# DS18B20_with_DS2480B_MAX233_V4.net
KiCad netlist of a schematic drawn in EAGLE
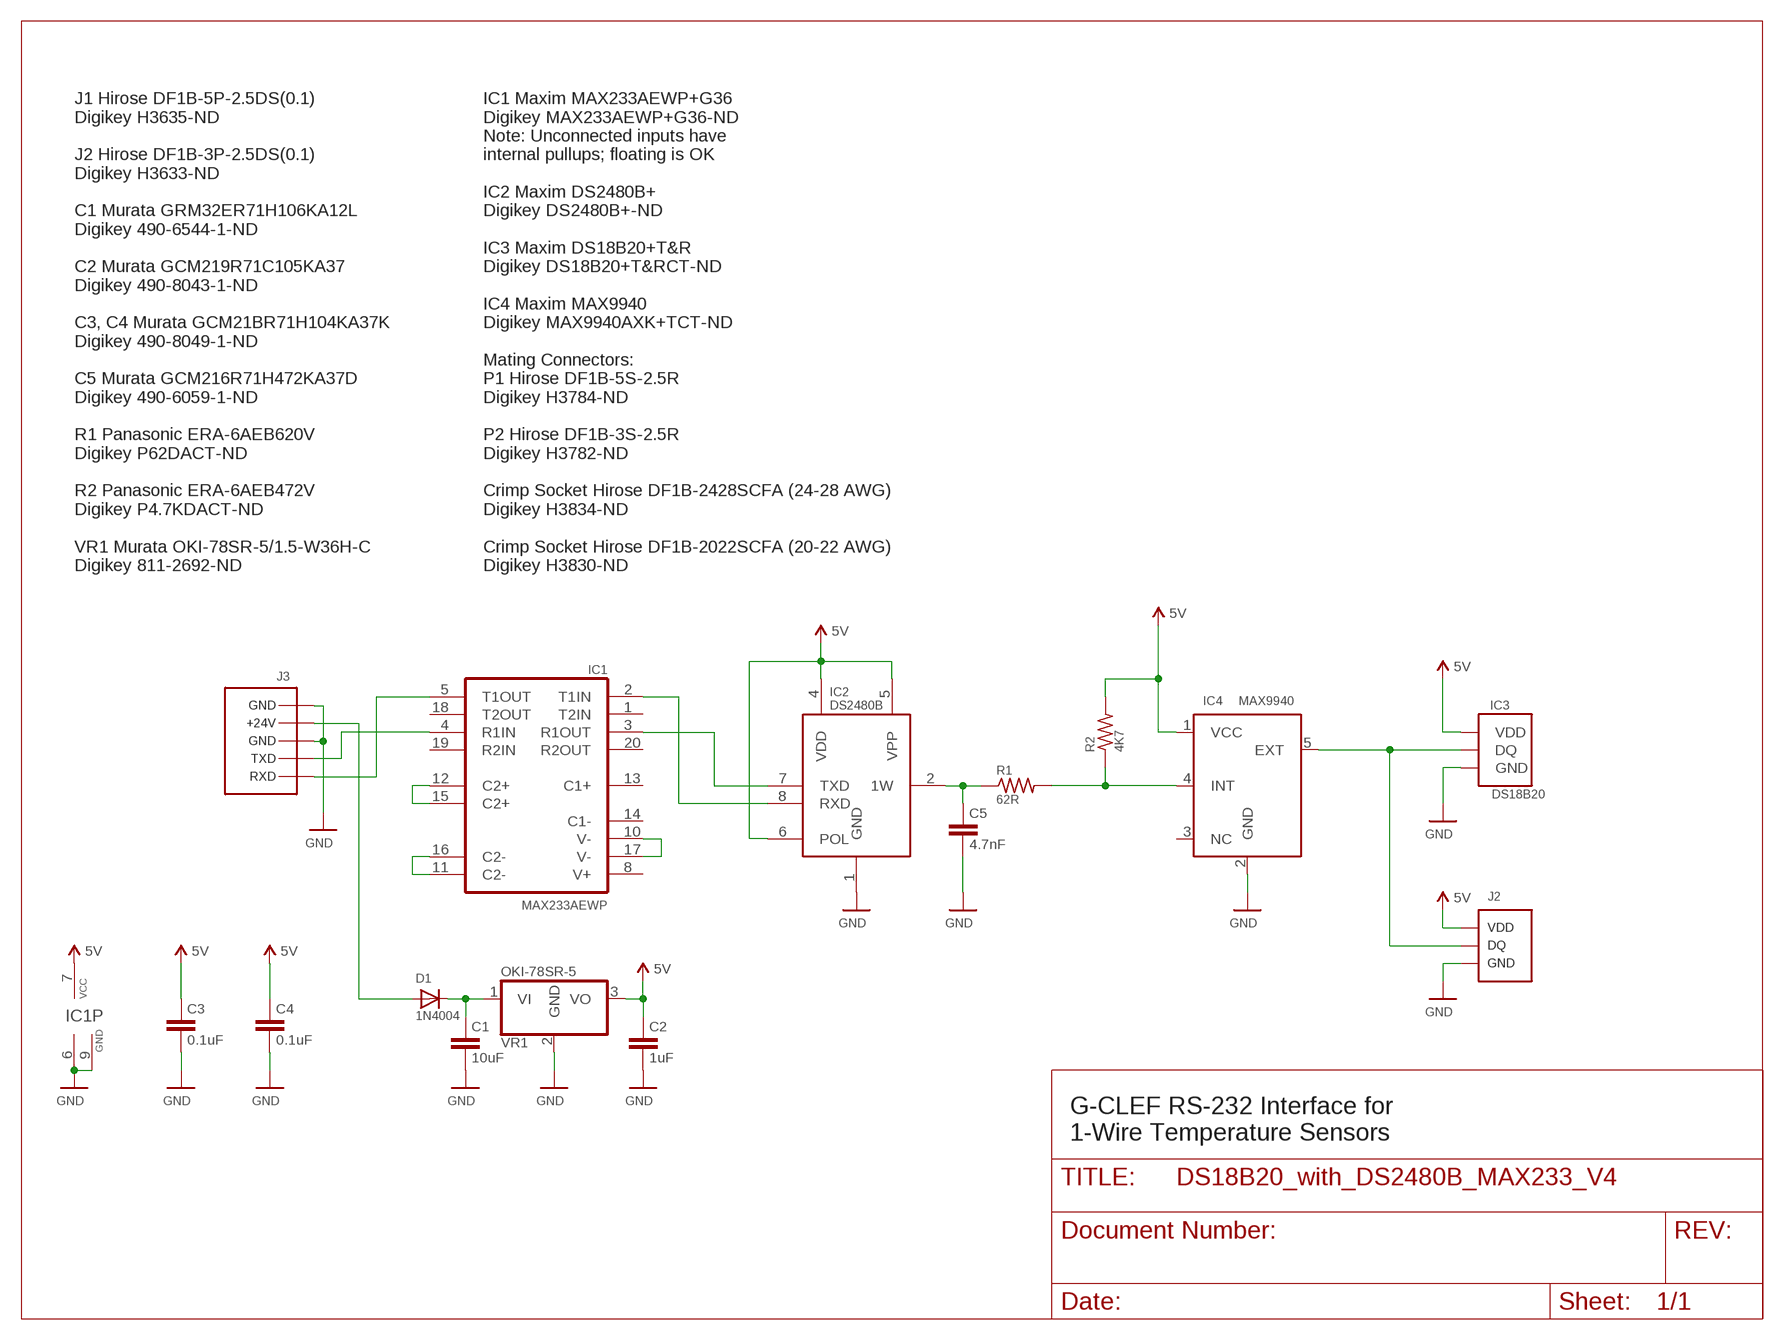
[diagram p0: schematic, sheet 1]

(export (version "E")
  (design (tool "Eeschema 10.0.6"))
  (components
    (comp (ref "C1")
      (value "10uF")
      (footprint "eagle-import:CAPC3225X270N")
      (libsource (lib "eagle-import") (part "C-UNPOL1210-CAP"))
    )
    (comp (ref "C2")
      (value "1uF")
      (footprint "eagle-import:CAPC2013X135N")
      (libsource (lib "eagle-import") (part "C-UNPOL0805-CAP"))
    )
    (comp (ref "C3")
      (value "0.1uF")
      (footprint "eagle-import:CAPC2013X135N")
      (libsource (lib "eagle-import") (part "C-UNPOL0805-CAP"))
    )
    (comp (ref "C4")
      (value "0.1uF")
      (footprint "eagle-import:CAPC2013X135N")
      (libsource (lib "eagle-import") (part "C-UNPOL0805-CAP"))
    )
    (comp (ref "C5")
      (value "4.7nF")
      (footprint "eagle-import:CAPC2013X135N")
      (libsource (lib "eagle-import") (part "C-UNPOL0805-CAP"))
    )
    (comp (ref "D1")
      (value "1N4004")
      (footprint "eagle-import:DO41-10")
      (libsource (lib "eagle-import") (part "1N4004"))
    )
    (comp (ref "IC1")
      (value "MAX233AEWP")
      (footprint "eagle-import:SO20L")
      (fields (field (name "MPN") "MAX233AEWP+G36"))
      (libsource (lib "eagle-import") (part "MAX233AEWP"))
    )
    (comp (ref "IC2")
      (value "DS2480B")
      (footprint "eagle-import:SO08")
      (libsource (lib "eagle-import") (part "DS2480B"))
    )
    (comp (ref "IC3")
      (value "DS18B20")
      (footprint "eagle-import:TO92-")
      (libsource (lib "eagle-import") (part "DS18B20"))
    )
    (comp (ref "IC4")
      (value "MAX9940")
      (footprint "eagle-import:SC70-5L")
      (libsource (lib "eagle-import") (part "MAX9940"))
    )
    (comp (ref "J2")
      (value "DF1B-3P")
      (footprint "eagle-import:DF1B-3P")
      (libsource (lib "eagle-import") (part "DF1B-3P"))
    )
    (comp (ref "J3")
      (value "DF1B-5P")
      (footprint "eagle-import:DF1B-5P")
      (libsource (lib "eagle-import") (part "DF1B-5P"))
    )
    (comp (ref "R1")
      (value "62R")
      (footprint "eagle-import:RESISTOR-0805")
      (libsource (lib "eagle-import") (part "RESISTOR-0805"))
    )
    (comp (ref "R2")
      (value "4K7")
      (footprint "eagle-import:RESISTOR-0805")
      (libsource (lib "eagle-import") (part "RESISTOR-0805"))
    )
    (comp (ref "VR1")
      (value "OKI-78SR-5")
      (footprint "eagle-import:OKI-78SR")
      (libsource (lib "eagle-import") (part "OKI-78SRH"))
    )
  )
  (nets
    (net (code "1") (name "5V") (class "Default")
      (node (ref "C2") (pin "1") (pinfunction "1_1") (pintype "passive"))
      (node (ref "C3") (pin "1") (pinfunction "1_1") (pintype "passive"))
      (node (ref "C4") (pin "1") (pinfunction "1_1") (pintype "passive"))
      (node (ref "IC1") (pin "7") (pinfunction "VCC_7") (pintype "power_in"))
      (node (ref "IC2") (pin "4") (pinfunction "VDD_4") (pintype "power_in"))
      (node (ref "IC2") (pin "5") (pinfunction "VPP_5") (pintype "power_in"))
      (node (ref "IC2") (pin "6") (pinfunction "POL_6") (pintype "input"))
      (node (ref "IC3") (pin "3") (pinfunction "VDD_3") (pintype "bidirectional"))
      (node (ref "IC4") (pin "1") (pinfunction "VCC_1") (pintype "power_in"))
      (node (ref "J2") (pin "P$3") (pinfunction "P$3_P$3") (pintype "bidirectional"))
      (node (ref "R2") (pin "2") (pinfunction "2_2") (pintype "passive"))
      (node (ref "VR1") (pin "3") (pinfunction "VO_3") (pintype "passive"))
    )
    (net (code "2") (name "GND") (class "Default")
      (node (ref "C1") (pin "2") (pinfunction "2_2") (pintype "passive"))
      (node (ref "C2") (pin "2") (pinfunction "2_2") (pintype "passive"))
      (node (ref "C3") (pin "2") (pinfunction "2_2") (pintype "passive"))
      (node (ref "C4") (pin "2") (pinfunction "2_2") (pintype "passive"))
      (node (ref "C5") (pin "2") (pinfunction "2_2") (pintype "passive"))
      (node (ref "IC1") (pin "6") (pinfunction "GND_6") (pintype "power_in"))
      (node (ref "IC1") (pin "9") (pinfunction "GND_9") (pintype "power_in"))
      (node (ref "IC2") (pin "1") (pinfunction "GND_1") (pintype "power_in"))
      (node (ref "IC3") (pin "1") (pinfunction "GND_1") (pintype "bidirectional"))
      (node (ref "IC4") (pin "2") (pinfunction "GND_2") (pintype "power_in"))
      (node (ref "J2") (pin "P$1") (pinfunction "P$1_P$1") (pintype "bidirectional"))
      (node (ref "J3") (pin "P$3") (pinfunction "P$3_P$3") (pintype "bidirectional"))
      (node (ref "J3") (pin "P$5") (pinfunction "P$5_P$5") (pintype "bidirectional"))
      (node (ref "VR1") (pin "2") (pinfunction "GND_2") (pintype "passive"))
    )
    (net (code "3") (name "Net-(D1-PadA)") (class "Default")
      (node (ref "D1") (pin "A") (pinfunction "A_A") (pintype "passive"))
      (node (ref "J3") (pin "P$4") (pinfunction "P$4_P$4") (pintype "bidirectional"))
    )
    (net (code "4") (name "Net-(IC1A-C2+-Pad12)") (class "Default")
      (node (ref "IC1") (pin "12") (pinfunction "C2+_12") (pintype "bidirectional"))
      (node (ref "IC1") (pin "15") (pinfunction "C2+_15") (pintype "bidirectional"))
    )
    (net (code "5") (name "Net-(IC1A-C2--Pad11)") (class "Default")
      (node (ref "IC1") (pin "11") (pinfunction "C2-_11") (pintype "bidirectional"))
      (node (ref "IC1") (pin "16") (pinfunction "C2-_16") (pintype "bidirectional"))
    )
    (net (code "6") (name "Net-(IC1A-R1IN)") (class "Default")
      (node (ref "IC1") (pin "4") (pinfunction "R1IN_4") (pintype "input"))
      (node (ref "J3") (pin "P$2") (pinfunction "P$2_P$2") (pintype "bidirectional"))
    )
    (net (code "7") (name "Net-(IC1A-R1OUT)") (class "Default")
      (node (ref "IC1") (pin "3") (pinfunction "R1OUT_3") (pintype "output"))
      (node (ref "IC2") (pin "7") (pinfunction "TXD_7") (pintype "input"))
    )
    (net (code "8") (name "Net-(IC1A-T1IN)") (class "Default")
      (node (ref "IC1") (pin "2") (pinfunction "T1IN_2") (pintype "input"))
      (node (ref "IC2") (pin "8") (pinfunction "RXD_8") (pintype "output"))
    )
    (net (code "9") (name "Net-(IC1A-T1OUT)") (class "Default")
      (node (ref "IC1") (pin "5") (pinfunction "T1OUT_5") (pintype "output"))
      (node (ref "J3") (pin "P$1") (pinfunction "P$1_P$1") (pintype "bidirectional"))
    )
    (net (code "10") (name "Net-(IC1A-V--Pad10)") (class "Default")
      (node (ref "IC1") (pin "10") (pinfunction "V-_10") (pintype "bidirectional"))
      (node (ref "IC1") (pin "17") (pinfunction "V-_17") (pintype "bidirectional"))
    )
    (net (code "11") (name "Net-(IC2-1W)") (class "Default")
      (node (ref "C5") (pin "1") (pinfunction "1_1") (pintype "passive"))
      (node (ref "IC2") (pin "2") (pinfunction "1W_2") (pintype "open_collector"))
      (node (ref "R1") (pin "1") (pinfunction "1_1") (pintype "passive"))
    )
    (net (code "12") (name "Net-(IC3-DQ)") (class "Default")
      (node (ref "IC3") (pin "2") (pinfunction "DQ_2") (pintype "bidirectional"))
      (node (ref "IC4") (pin "5") (pinfunction "EXT_5") (pintype "output"))
      (node (ref "J2") (pin "P$2") (pinfunction "P$2_P$2") (pintype "bidirectional"))
    )
    (net (code "13") (name "Net-(IC4-INT)") (class "Default")
      (node (ref "IC4") (pin "4") (pinfunction "INT_4") (pintype "input"))
      (node (ref "R1") (pin "2") (pinfunction "2_2") (pintype "passive"))
      (node (ref "R2") (pin "1") (pinfunction "1_1") (pintype "passive"))
    )
    (net (code "14") (name "Net-(VR1-VI)") (class "Default")
      (node (ref "C1") (pin "1") (pinfunction "1_1") (pintype "passive"))
      (node (ref "D1") (pin "C") (pinfunction "C_C") (pintype "passive"))
      (node (ref "VR1") (pin "1") (pinfunction "VI_1") (pintype "input"))
    )
    (net (code "15") (name "unconnected-(IC1A-C1+-Pad13)") (class "Default")
      (node (ref "IC1") (pin "13") (pinfunction "C1+_13") (pintype "bidirectional"))
    )
    (net (code "16") (name "unconnected-(IC1A-C1--Pad14)") (class "Default")
      (node (ref "IC1") (pin "14") (pinfunction "C1-_14") (pintype "bidirectional"))
    )
    (net (code "17") (name "unconnected-(IC1A-R2IN-Pad19)") (class "Default")
      (node (ref "IC1") (pin "19") (pinfunction "R2IN_19") (pintype "input"))
    )
    (net (code "18") (name "unconnected-(IC1A-R2OUT-Pad20)") (class "Default")
      (node (ref "IC1") (pin "20") (pinfunction "R2OUT_20") (pintype "output"))
    )
    (net (code "19") (name "unconnected-(IC1A-T2IN-Pad1)") (class "Default")
      (node (ref "IC1") (pin "1") (pinfunction "T2IN_1") (pintype "input"))
    )
    (net (code "20") (name "unconnected-(IC1A-T2OUT-Pad18)") (class "Default")
      (node (ref "IC1") (pin "18") (pinfunction "T2OUT_18") (pintype "output"))
    )
    (net (code "21") (name "unconnected-(IC1A-V+-Pad8)") (class "Default")
      (node (ref "IC1") (pin "8") (pinfunction "V+_8") (pintype "bidirectional"))
    )
    (net (code "22") (name "unconnected-(IC4-NC-Pad3)") (class "Default")
      (node (ref "IC4") (pin "3") (pinfunction "NC_3") (pintype "no_connect"))
    )
  )
)
